# 06_-DDR2_Interface.net
KiCad netlist of a schematic drawn in Altium Designer
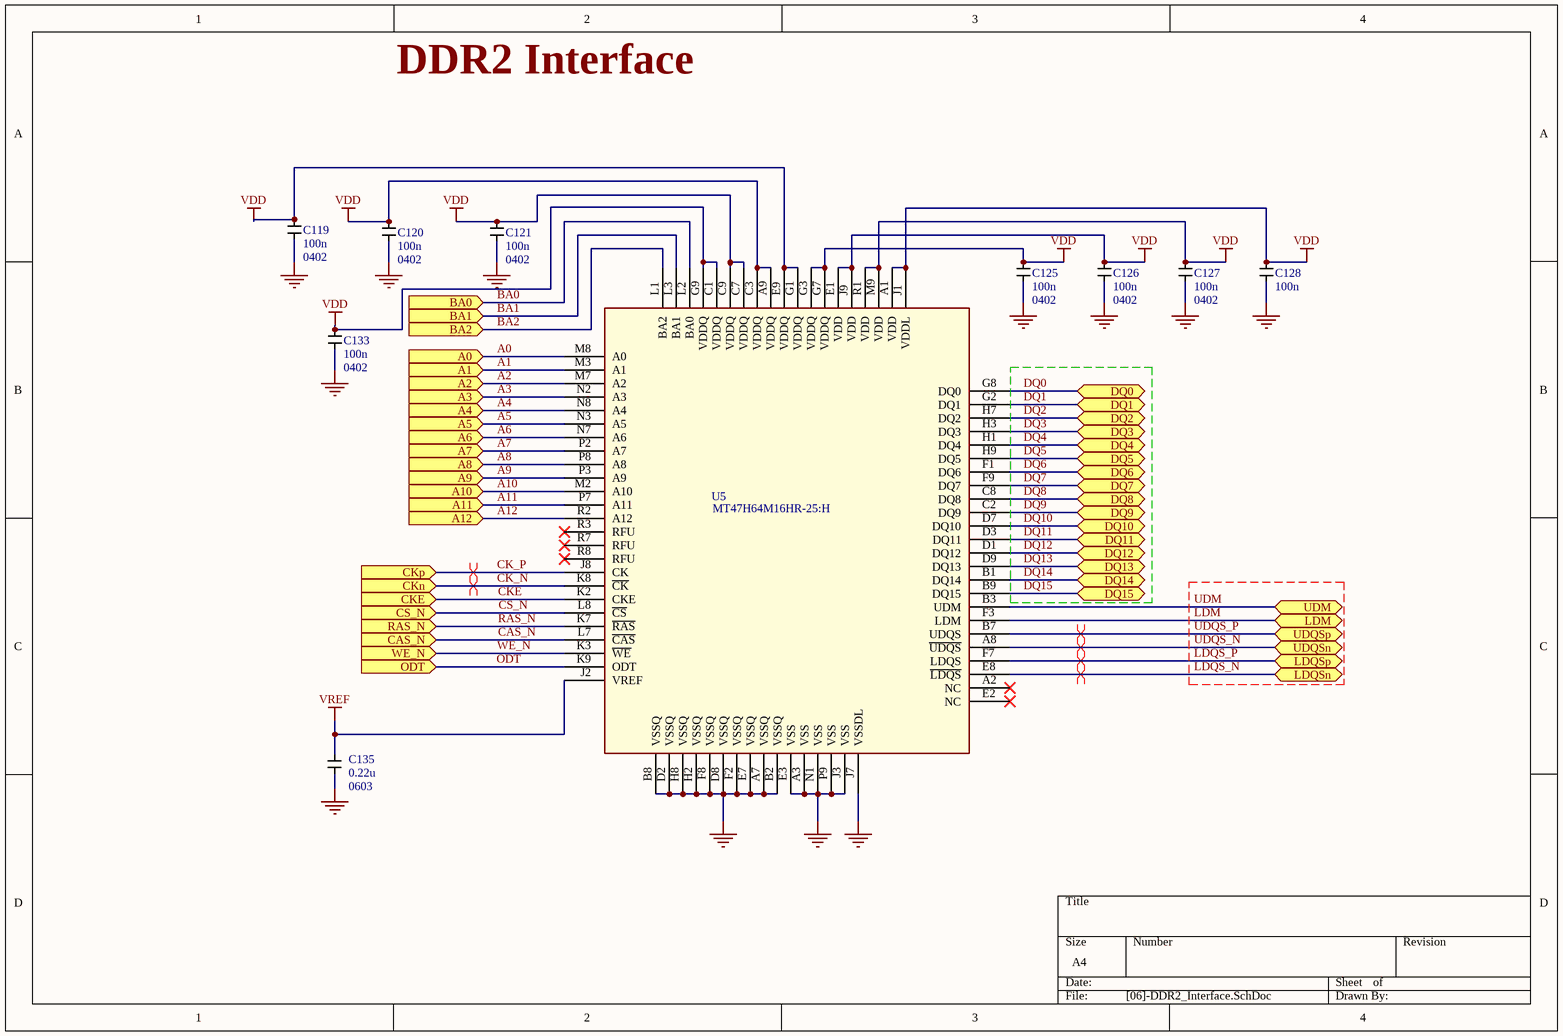
[diagram p0: [06]-DDR2_Interface.SchDoc]

(export (version "E")
  (design (tool "Eeschema 10.0.6"))
  (components
    (comp (ref "C119")
      (value "100n")
      (footprint "*CAPC1005X60N")
      (fields (field (name "PCB STAKE") "0402"))
      (libsource (lib "04023C104KAT2A_0402") (part "Component_1"))
    )
    (comp (ref "C120")
      (value "100n")
      (footprint "*CAPC1005X60N")
      (fields (field (name "PCB STAKE") "0402"))
      (libsource (lib "04023C104KAT2A_0402") (part "Component_1"))
    )
    (comp (ref "C121")
      (value "100n")
      (footprint "*CAPC1005X60N")
      (fields (field (name "PCB STAKE") "0402"))
      (libsource (lib "04023C104KAT2A_0402") (part "Component_1"))
    )
    (comp (ref "C125")
      (value "100n")
      (footprint "*CAPC1005X60N")
      (fields (field (name "PCB STAKE") "0402"))
      (libsource (lib "04023C104KAT2A_0402") (part "Component_1"))
    )
    (comp (ref "C126")
      (value "100n")
      (footprint "*CAPC1005X60N")
      (fields (field (name "PCB STAKE") "0402"))
      (libsource (lib "04023C104KAT2A_0402") (part "Component_1"))
    )
    (comp (ref "C127")
      (value "100n")
      (footprint "*CAPC1005X60N")
      (fields (field (name "PCB STAKE") "0402"))
      (libsource (lib "04023C104KAT2A_0402") (part "Component_1"))
    )
    (comp (ref "C128")
      (value "100n")
      (footprint "*CAPC1005X60N")
      (libsource (lib "04023C104KAT2A_0402") (part "Component_1"))
    )
    (comp (ref "C133")
      (value "100n")
      (footprint "*CAPC1005X60N")
      (fields (field (name "PCB STAKE") "0402"))
      (libsource (lib "04023C104KAT2A_0402") (part "Component_1"))
    )
    (comp (ref "C135")
      (value "0.22u")
      (footprint "*0603")
      (fields (field (name "PCB LAYER:") "0603"))
      (libsource (lib "0603YC105KAT2A") (part "Component_1"))
    )
    (comp (ref "U5")
      (value "MT47H64M16HR-25:H")
      (footprint "BGA84CP80_15X9_1250X900X120B45N")
      (description "DDR2 SDRAM with configuration of 64 Meg * 16 bits.")
      (fields (field (name "DESIGNER") "Faheem Minhas") (field (name "DATE CREATED") "18-Janruary-2019"))
      (libsource (lib "MT47H64M16NF_25E IT_M") (part "micron_ddr2_sdram"))
    )
  )
  (nets
    (net (code "1") (name "/A0") (class "Default")
      (node (ref "U5") (pin "M8") (pinfunction "A0_M8") (pintype "passive"))
    )
    (net (code "2") (name "/A1") (class "Default")
      (node (ref "U5") (pin "M3") (pinfunction "A1_M3") (pintype "passive"))
    )
    (net (code "3") (name "/A2") (class "Default")
      (node (ref "U5") (pin "M7") (pinfunction "A2_M7") (pintype "passive"))
    )
    (net (code "4") (name "/A3") (class "Default")
      (node (ref "U5") (pin "N2") (pinfunction "A3_N2") (pintype "passive"))
    )
    (net (code "5") (name "/A4") (class "Default")
      (node (ref "U5") (pin "N8") (pinfunction "A4_N8") (pintype "passive"))
    )
    (net (code "6") (name "/A5") (class "Default")
      (node (ref "U5") (pin "N3") (pinfunction "A5_N3") (pintype "passive"))
    )
    (net (code "7") (name "/A6") (class "Default")
      (node (ref "U5") (pin "N7") (pinfunction "A6_N7") (pintype "passive"))
    )
    (net (code "8") (name "/A7") (class "Default")
      (node (ref "U5") (pin "P2") (pinfunction "A7_P2") (pintype "passive"))
    )
    (net (code "9") (name "/A8") (class "Default")
      (node (ref "U5") (pin "P8") (pinfunction "A8_P8") (pintype "passive"))
    )
    (net (code "10") (name "/A9") (class "Default")
      (node (ref "U5") (pin "P3") (pinfunction "A9_P3") (pintype "passive"))
    )
    (net (code "11") (name "/A10") (class "Default")
      (node (ref "U5") (pin "M2") (pinfunction "A10_M2") (pintype "passive"))
    )
    (net (code "12") (name "/A11") (class "Default")
      (node (ref "U5") (pin "P7") (pinfunction "A11_P7") (pintype "passive"))
    )
    (net (code "13") (name "/A12") (class "Default")
      (node (ref "U5") (pin "R2") (pinfunction "A12_R2") (pintype "passive"))
    )
    (net (code "14") (name "/BA0") (class "Default")
      (node (ref "U5") (pin "L2") (pinfunction "BA0_L2") (pintype "passive"))
    )
    (net (code "15") (name "/BA1") (class "Default")
      (node (ref "U5") (pin "L3") (pinfunction "BA1_L3") (pintype "passive"))
    )
    (net (code "16") (name "/BA2") (class "Default")
      (node (ref "U5") (pin "L1") (pinfunction "BA2_L1") (pintype "passive"))
    )
    (net (code "17") (name "/CAS_N") (class "Default")
      (node (ref "U5") (pin "L7") (pinfunction "~{CAS}_L7") (pintype "passive"))
    )
    (net (code "18") (name "/CKE") (class "Default")
      (node (ref "U5") (pin "K2") (pinfunction "CKE_K2") (pintype "passive"))
    )
    (net (code "19") (name "/CK_N") (class "Default")
      (node (ref "U5") (pin "K8") (pinfunction "~{CK}_K8") (pintype "passive"))
    )
    (net (code "20") (name "/CK_P") (class "Default")
      (node (ref "U5") (pin "J8") (pinfunction "CK_J8") (pintype "passive"))
    )
    (net (code "21") (name "/CS_N") (class "Default")
      (node (ref "U5") (pin "L8") (pinfunction "~{CS}_L8") (pintype "passive"))
    )
    (net (code "22") (name "/DQ0") (class "Default")
      (node (ref "U5") (pin "G8") (pinfunction "DQ0_G8") (pintype "passive"))
    )
    (net (code "23") (name "/DQ1") (class "Default")
      (node (ref "U5") (pin "G2") (pinfunction "DQ1_G2") (pintype "passive"))
    )
    (net (code "24") (name "/DQ2") (class "Default")
      (node (ref "U5") (pin "H7") (pinfunction "DQ2_H7") (pintype "passive"))
    )
    (net (code "25") (name "/DQ3") (class "Default")
      (node (ref "U5") (pin "H3") (pinfunction "DQ3_H3") (pintype "passive"))
    )
    (net (code "26") (name "/DQ4") (class "Default")
      (node (ref "U5") (pin "H1") (pinfunction "DQ4_H1") (pintype "passive"))
    )
    (net (code "27") (name "/DQ5") (class "Default")
      (node (ref "U5") (pin "H9") (pinfunction "DQ5_H9") (pintype "passive"))
    )
    (net (code "28") (name "/DQ6") (class "Default")
      (node (ref "U5") (pin "F1") (pinfunction "DQ6_F1") (pintype "passive"))
    )
    (net (code "29") (name "/DQ7") (class "Default")
      (node (ref "U5") (pin "F9") (pinfunction "DQ7_F9") (pintype "passive"))
    )
    (net (code "30") (name "/DQ8") (class "Default")
      (node (ref "U5") (pin "C8") (pinfunction "DQ8_C8") (pintype "passive"))
    )
    (net (code "31") (name "/DQ9") (class "Default")
      (node (ref "U5") (pin "C2") (pinfunction "DQ9_C2") (pintype "passive"))
    )
    (net (code "32") (name "/DQ10") (class "Default")
      (node (ref "U5") (pin "D7") (pinfunction "DQ10_D7") (pintype "passive"))
    )
    (net (code "33") (name "/DQ11") (class "Default")
      (node (ref "U5") (pin "D3") (pinfunction "DQ11_D3") (pintype "passive"))
    )
    (net (code "34") (name "/DQ12") (class "Default")
      (node (ref "U5") (pin "D1") (pinfunction "DQ12_D1") (pintype "passive"))
    )
    (net (code "35") (name "/DQ13") (class "Default")
      (node (ref "U5") (pin "D9") (pinfunction "DQ13_D9") (pintype "passive"))
    )
    (net (code "36") (name "/DQ14") (class "Default")
      (node (ref "U5") (pin "B1") (pinfunction "DQ14_B1") (pintype "passive"))
    )
    (net (code "37") (name "/DQ15") (class "Default")
      (node (ref "U5") (pin "B9") (pinfunction "DQ15_B9") (pintype "passive"))
    )
    (net (code "38") (name "/LDM") (class "Default")
      (node (ref "U5") (pin "F3") (pinfunction "LDM_F3") (pintype "passive"))
    )
    (net (code "39") (name "/LDQS_N") (class "Default")
      (node (ref "U5") (pin "E8") (pinfunction "~{LDQS}_E8") (pintype "passive"))
    )
    (net (code "40") (name "/LDQS_P") (class "Default")
      (node (ref "U5") (pin "F7") (pinfunction "LDQS_F7") (pintype "passive"))
    )
    (net (code "41") (name "/ODT") (class "Default")
      (node (ref "U5") (pin "K9") (pinfunction "ODT_K9") (pintype "passive"))
    )
    (net (code "42") (name "/RAS_N") (class "Default")
      (node (ref "U5") (pin "K7") (pinfunction "~{RAS}_K7") (pintype "passive"))
    )
    (net (code "43") (name "/UDM") (class "Default")
      (node (ref "U5") (pin "B3") (pinfunction "UDM_B3") (pintype "passive"))
    )
    (net (code "44") (name "/UDQS_N") (class "Default")
      (node (ref "U5") (pin "A8") (pinfunction "~{UDQS}_A8") (pintype "passive"))
    )
    (net (code "45") (name "/UDQS_P") (class "Default")
      (node (ref "U5") (pin "B7") (pinfunction "UDQS_B7") (pintype "passive"))
    )
    (net (code "46") (name "/WE_N") (class "Default")
      (node (ref "U5") (pin "K3") (pinfunction "~{WE}_K3") (pintype "passive"))
    )
    (net (code "47") (name "GND") (class "Default")
      (node (ref "C119") (pin "2") (pinfunction "2_2") (pintype "passive"))
      (node (ref "C120") (pin "2") (pinfunction "2_2") (pintype "passive"))
      (node (ref "C121") (pin "2") (pinfunction "2_2") (pintype "passive"))
      (node (ref "C125") (pin "2") (pinfunction "2_2") (pintype "passive"))
      (node (ref "C126") (pin "2") (pinfunction "2_2") (pintype "passive"))
      (node (ref "C127") (pin "2") (pinfunction "2_2") (pintype "passive"))
      (node (ref "C128") (pin "2") (pinfunction "2_2") (pintype "passive"))
      (node (ref "C133") (pin "2") (pinfunction "2_2") (pintype "passive"))
      (node (ref "C135") (pin "1") (pinfunction "1_1") (pintype "passive"))
      (node (ref "U5") (pin "A3") (pinfunction "VSS_A3") (pintype "power_in"))
      (node (ref "U5") (pin "A7") (pinfunction "VSSQ_A7") (pintype "power_in"))
      (node (ref "U5") (pin "B2") (pinfunction "VSSQ_B2") (pintype "power_in"))
      (node (ref "U5") (pin "B8") (pinfunction "VSSQ_B8") (pintype "power_in"))
      (node (ref "U5") (pin "D2") (pinfunction "VSSQ_D2") (pintype "power_in"))
      (node (ref "U5") (pin "D8") (pinfunction "VSSQ_D8") (pintype "power_in"))
      (node (ref "U5") (pin "E3") (pinfunction "VSS_E3") (pintype "power_in"))
      (node (ref "U5") (pin "E7") (pinfunction "VSSQ_E7") (pintype "power_in"))
      (node (ref "U5") (pin "F2") (pinfunction "VSSQ_F2") (pintype "power_in"))
      (node (ref "U5") (pin "F8") (pinfunction "VSSQ_F8") (pintype "power_in"))
      (node (ref "U5") (pin "H2") (pinfunction "VSSQ_H2") (pintype "power_in"))
      (node (ref "U5") (pin "H8") (pinfunction "VSSQ_H8") (pintype "power_in"))
      (node (ref "U5") (pin "J3") (pinfunction "VSS_J3") (pintype "power_in"))
      (node (ref "U5") (pin "J7") (pinfunction "VSSDL_J7") (pintype "power_in"))
      (node (ref "U5") (pin "N1") (pinfunction "VSS_N1") (pintype "power_in"))
      (node (ref "U5") (pin "P9") (pinfunction "VSS_P9") (pintype "power_in"))
    )
    (net (code "48") (name "VDD") (class "Default")
      (node (ref "C119") (pin "1") (pinfunction "1_1") (pintype "passive"))
      (node (ref "C120") (pin "1") (pinfunction "1_1") (pintype "passive"))
      (node (ref "C121") (pin "1") (pinfunction "1_1") (pintype "passive"))
      (node (ref "C125") (pin "1") (pinfunction "1_1") (pintype "passive"))
      (node (ref "C126") (pin "1") (pinfunction "1_1") (pintype "passive"))
      (node (ref "C127") (pin "1") (pinfunction "1_1") (pintype "passive"))
      (node (ref "C128") (pin "1") (pinfunction "1_1") (pintype "passive"))
      (node (ref "C133") (pin "1") (pinfunction "1_1") (pintype "passive"))
      (node (ref "U5") (pin "A1") (pinfunction "VDD_A1") (pintype "power_in"))
      (node (ref "U5") (pin "A9") (pinfunction "VDDQ_A9") (pintype "power_in"))
      (node (ref "U5") (pin "C1") (pinfunction "VDDQ_C1") (pintype "power_in"))
      (node (ref "U5") (pin "C3") (pinfunction "VDDQ_C3") (pintype "power_in"))
      (node (ref "U5") (pin "C7") (pinfunction "VDDQ_C7") (pintype "power_in"))
      (node (ref "U5") (pin "C9") (pinfunction "VDDQ_C9") (pintype "power_in"))
      (node (ref "U5") (pin "E1") (pinfunction "VDD_E1") (pintype "power_in"))
      (node (ref "U5") (pin "E9") (pinfunction "VDDQ_E9") (pintype "power_in"))
      (node (ref "U5") (pin "G1") (pinfunction "VDDQ_G1") (pintype "power_in"))
      (node (ref "U5") (pin "G3") (pinfunction "VDDQ_G3") (pintype "power_in"))
      (node (ref "U5") (pin "G7") (pinfunction "VDDQ_G7") (pintype "power_in"))
      (node (ref "U5") (pin "G9") (pinfunction "VDDQ_G9") (pintype "power_in"))
      (node (ref "U5") (pin "J1") (pinfunction "VDDL_J1") (pintype "power_in"))
      (node (ref "U5") (pin "J9") (pinfunction "VDD_J9") (pintype "power_in"))
      (node (ref "U5") (pin "M9") (pinfunction "VDD_M9") (pintype "power_in"))
      (node (ref "U5") (pin "R1") (pinfunction "VDD_R1") (pintype "power_in"))
    )
    (net (code "49") (name "VREF") (class "Default")
      (node (ref "C135") (pin "2") (pinfunction "2_2") (pintype "passive"))
      (node (ref "U5") (pin "J2") (pinfunction "VREF_J2") (pintype "power_in"))
    )
    (net (code "50") (name "unconnected-(U5-NC-PadA2)") (class "Default")
      (node (ref "U5") (pin "A2") (pinfunction "NC_A2") (pintype "open_emitter+no_connect"))
    )
    (net (code "51") (name "unconnected-(U5-NC-PadE2)") (class "Default")
      (node (ref "U5") (pin "E2") (pinfunction "NC_E2") (pintype "open_emitter+no_connect"))
    )
    (net (code "52") (name "unconnected-(U5-RFU-PadR3)") (class "Default")
      (node (ref "U5") (pin "R3") (pinfunction "RFU_R3") (pintype "open_collector+no_connect"))
    )
    (net (code "53") (name "unconnected-(U5-RFU-PadR7)") (class "Default")
      (node (ref "U5") (pin "R7") (pinfunction "RFU_R7") (pintype "open_collector+no_connect"))
    )
    (net (code "54") (name "unconnected-(U5-RFU-PadR8)") (class "Default")
      (node (ref "U5") (pin "R8") (pinfunction "RFU_R8") (pintype "open_collector+no_connect"))
    )
  )
)
